# Sheet1.net
KiCad netlist of a schematic drawn in Altium Designer
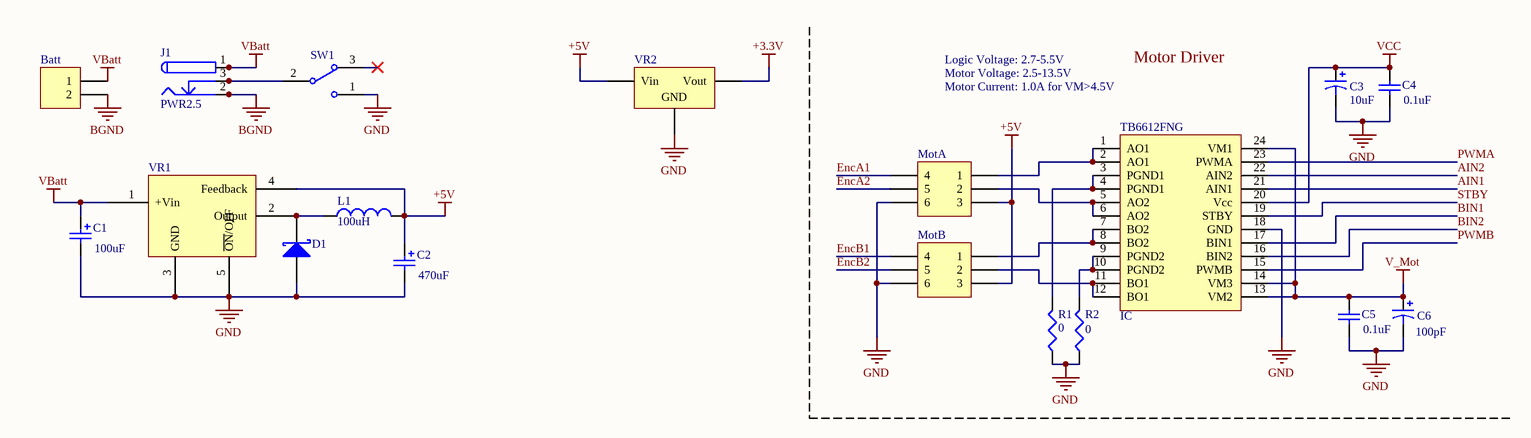
[diagram p0: Sheet1.SchDoc]

(export (version "E")
  (design (tool "Eeschema 10.0.6"))
  (components
    (comp (ref "Batt")
      (value "Header 2")
      (footprint "HDR1X2")
      (description "Header, 2-Pin")
      (fields (field (name "PUBLISHER") "Altium Limited"))
      (libsource (lib "Miscellaneous Connectors") (part "Header 2"))
    )
    (comp (ref "C1")
      (value "100uF")
      (footprint "Capacitor")
      (description "Polarized Capacitor (Radial)")
      (fields (field (name "Comment") "Cap Pol2") (field (name "PUBLISHER") "Altium Limited"))
      (libsource (lib "Miscellaneous Devices") (part "Cap Pol2"))
    )
    (comp (ref "C2")
      (value "470uF")
      (footprint "Capacitor - 8x10.5")
      (description "Polarized Capacitor (Radial)")
      (fields (field (name "Comment") "Cap Pol2") (field (name "PUBLISHER") "Altium Limited"))
      (libsource (lib "Miscellaneous Devices") (part "Cap Pol2"))
    )
    (comp (ref "C3")
      (value "10uF")
      (footprint "C0805")
      (description "Polarized Capacitor (Surface Mount)")
      (fields (field (name "Comment") "Cap Pol3") (field (name "PUBLISHER") "Altium Limited"))
      (libsource (lib "Miscellaneous Devices") (part "Cap Pol3"))
    )
    (comp (ref "C4")
      (value "0.1uF")
      (footprint "C1206")
      (description "Capacitor (Semiconductor SIM Model)")
      (fields (field (name "Comment") "Cap Semi") (field (name "PUBLISHER") "Altium Limited"))
      (libsource (lib "Miscellaneous Devices") (part "Cap Semi"))
    )
    (comp (ref "C5")
      (value "0.1uF")
      (footprint "C1206")
      (description "Capacitor (Semiconductor SIM Model)")
      (fields (field (name "Comment") "Cap Semi") (field (name "PUBLISHER") "Altium Limited"))
      (libsource (lib "Miscellaneous Devices") (part "Cap Semi"))
    )
    (comp (ref "C6")
      (value "100pF")
      (footprint "C0805")
      (description "Polarized Capacitor (Surface Mount)")
      (fields (field (name "Comment") "Cap Pol3") (field (name "PUBLISHER") "Altium Limited"))
      (libsource (lib "Miscellaneous Devices") (part "Cap Pol3"))
    )
    (comp (ref "D1")
      (value "D Schottky")
      (footprint "SMB")
      (description "Schottky Diode")
      (fields (field (name "PUBLISHER") "Altium Limited"))
      (libsource (lib "Miscellaneous Devices") (part "D Schottky"))
    )
    (comp (ref "J1")
      (value "PWR2.5")
      (footprint "KLD-0202")
      (description "Low Voltage Power Supply Connector")
      (fields (field (name "PUBLISHER") "Altium Limited"))
      (libsource (lib "Miscellaneous Connectors") (part "PWR2.5"))
    )
    (comp (ref "L1")
      (value "100uH")
      (footprint "0402-A")
      (description "Inductor")
      (fields (field (name "PUBLISHER") "Altium Limited"))
      (libsource (lib "Miscellaneous Devices") (part "Inductor"))
    )
    (comp (ref "MotA")
      (value "Header 3X2A")
      (footprint "HDR2X3_CEN")
      (description "Header, 3-Pin, Dual row")
      (fields (field (name "PUBLISHER") "Altium Limited"))
      (libsource (lib "Miscellaneous Connectors") (part "Header 3X2A"))
    )
    (comp (ref "MotB")
      (value "Header 3X2A")
      (footprint "HDR2X3_CEN")
      (description "Header, 3-Pin, Dual row")
      (fields (field (name "PUBLISHER") "Altium Limited"))
      (libsource (lib "Miscellaneous Connectors") (part "Header 3X2A"))
    )
    (comp (ref "R1")
      (value "0")
      (footprint "J1-0603")
      (description "Resistor")
      (fields (field (name "Comment") "Shunt Resistor") (field (name "PUBLISHER") "Altium Limited"))
      (libsource (lib "Miscellaneous Devices") (part "Res3"))
    )
    (comp (ref "R2")
      (value "0")
      (footprint "J1-0603")
      (description "Resistor")
      (fields (field (name "Comment") "Shunt Resistor") (field (name "PUBLISHER") "Altium Limited"))
      (libsource (lib "Miscellaneous Devices") (part "Res3"))
    )
    (comp (ref "SW1")
      (value "SW-SPDT")
      (footprint "TL36WW15050")
      (description "SPDT Subminiature Toggle Switch, Right Angle Mounting, Vertical Actuation")
      (fields (field (name "PUBLISHER") "Altium Limited"))
      (libsource (lib "Miscellaneous Devices") (part "SW-SPDT"))
    )
    (comp (ref "TB6612FNG")
      (value "IC")
      (description "Motor Driver IC")
      (libsource (lib "iRat") (part "TB6612FNG IC"))
    )
    (comp (ref "VR1")
      (value "LM2576S-5.0NOPB")
      (footprint "LM2576S")
      (description "5V Switching Regulator")
      (libsource (lib "iRat") (part "LM2576S-5.0NOPB"))
    )
    (comp (ref "VR2")
      (value "3V Volt Reg")
      (footprint "D2PAK_N")
      (description "Voltage Regulator")
      (fields (field (name "PUBLISHER") "Altium Limited"))
      (libsource (lib "Miscellaneous Devices") (part "Volt Reg"))
    )
  )
  (nets
    (net (code "1") (name "+3.3V") (class "Default")
      (node (ref "VR2") (pin "3") (pinfunction "Vout_3") (pintype "passive"))
    )
    (net (code "2") (name "+5V") (class "Default")
      (node (ref "C2") (pin "1") (pinfunction "1_1") (pintype "passive"))
      (node (ref "L1") (pin "2") (pinfunction "2_2") (pintype "passive"))
      (node (ref "MotA") (pin "3") (pinfunction "3_3") (pintype "passive"))
      (node (ref "MotB") (pin "3") (pinfunction "3_3") (pintype "passive"))
      (node (ref "VR1") (pin "4") (pinfunction "Feedback_4") (pintype "passive"))
      (node (ref "VR2") (pin "1") (pinfunction "Vin_1") (pintype "passive"))
    )
    (net (code "3") (name "/AIN1") (class "Default")
      (node (ref "TB6612FNG") (pin "21") (pinfunction "AIN1_21") (pintype "passive"))
    )
    (net (code "4") (name "/AIN2") (class "Default")
      (node (ref "TB6612FNG") (pin "22") (pinfunction "AIN2_22") (pintype "passive"))
    )
    (net (code "5") (name "/BIN1") (class "Default")
      (node (ref "TB6612FNG") (pin "17") (pinfunction "BIN1_17") (pintype "passive"))
    )
    (net (code "6") (name "/BIN2") (class "Default")
      (node (ref "TB6612FNG") (pin "16") (pinfunction "BIN2_16") (pintype "passive"))
    )
    (net (code "7") (name "/EncA1") (class "Default")
      (node (ref "MotA") (pin "4") (pinfunction "4_4") (pintype "passive"))
    )
    (net (code "8") (name "/EncA2") (class "Default")
      (node (ref "MotA") (pin "5") (pinfunction "5_5") (pintype "passive"))
    )
    (net (code "9") (name "/EncB1") (class "Default")
      (node (ref "MotB") (pin "4") (pinfunction "4_4") (pintype "passive"))
    )
    (net (code "10") (name "/EncB2") (class "Default")
      (node (ref "MotB") (pin "5") (pinfunction "5_5") (pintype "passive"))
    )
    (net (code "11") (name "/PWMA") (class "Default")
      (node (ref "TB6612FNG") (pin "23") (pinfunction "PWMA_23") (pintype "passive"))
    )
    (net (code "12") (name "/PWMB") (class "Default")
      (node (ref "TB6612FNG") (pin "15") (pinfunction "PWMB_15") (pintype "passive"))
    )
    (net (code "13") (name "/STBY") (class "Default")
      (node (ref "TB6612FNG") (pin "19") (pinfunction "STBY_19") (pintype "passive"))
    )
    (net (code "14") (name "BGND") (class "Default")
      (node (ref "Batt") (pin "2") (pinfunction "2_2") (pintype "passive"))
      (node (ref "J1") (pin "2") (pinfunction "2_2") (pintype "power_in"))
      (node (ref "J1") (pin "2A") (pinfunction "2A_2A") (pintype "power_in"))
      (node (ref "J1") (pin "2B") (pinfunction "2B_2B") (pintype "power_in"))
    )
    (net (code "15") (name "GND") (class "Default")
      (node (ref "C1") (pin "2") (pinfunction "2_2") (pintype "passive"))
      (node (ref "C2") (pin "2") (pinfunction "2_2") (pintype "passive"))
      (node (ref "C3") (pin "2") (pinfunction "2_2") (pintype "passive"))
      (node (ref "C4") (pin "2") (pinfunction "2_2") (pintype "passive"))
      (node (ref "C5") (pin "2") (pinfunction "2_2") (pintype "passive"))
      (node (ref "C6") (pin "2") (pinfunction "2_2") (pintype "passive"))
      (node (ref "D1") (pin "1") (pinfunction "A_1") (pintype "passive"))
      (node (ref "MotA") (pin "6") (pinfunction "6_6") (pintype "passive"))
      (node (ref "MotB") (pin "6") (pinfunction "6_6") (pintype "passive"))
      (node (ref "R1") (pin "1") (pinfunction "1_1") (pintype "passive"))
      (node (ref "R2") (pin "1") (pinfunction "1_1") (pintype "passive"))
      (node (ref "SW1") (pin "1") (pinfunction "1_1") (pintype "passive"))
      (node (ref "TB6612FNG") (pin "18") (pinfunction "GND_18") (pintype "passive"))
      (node (ref "VR1") (pin "3") (pinfunction "GND_3") (pintype "passive"))
      (node (ref "VR1") (pin "5") (pinfunction "~{ON}/OFF_5") (pintype "passive"))
      (node (ref "VR2") (pin "2") (pinfunction "GND_2") (pintype "passive"))
    )
    (net (code "16") (name "Net-(D1-K)") (class "Default")
      (node (ref "D1") (pin "2") (pinfunction "K_2") (pintype "passive"))
      (node (ref "L1") (pin "1") (pinfunction "1_1") (pintype "passive"))
      (node (ref "VR1") (pin "2") (pinfunction "Output_2") (pintype "passive"))
    )
    (net (code "17") (name "Net-(J1-Pad3)") (class "Default")
      (node (ref "J1") (pin "3") (pinfunction "3_3") (pintype "power_in"))
      (node (ref "J1") (pin "3A") (pinfunction "3A_3A") (pintype "power_in"))
      (node (ref "J1") (pin "3B") (pinfunction "3B_3B") (pintype "power_in"))
      (node (ref "SW1") (pin "2") (pinfunction "2_2") (pintype "passive"))
    )
    (net (code "18") (name "Net-(MotA-Pad1)") (class "Default")
      (node (ref "MotA") (pin "1") (pinfunction "1_1") (pintype "passive"))
      (node (ref "TB6612FNG") (pin "1") (pinfunction "AO1_1") (pintype "passive"))
      (node (ref "TB6612FNG") (pin "2") (pinfunction "AO1_2") (pintype "passive"))
    )
    (net (code "19") (name "Net-(MotA-Pad2)") (class "Default")
      (node (ref "MotA") (pin "2") (pinfunction "2_2") (pintype "passive"))
      (node (ref "TB6612FNG") (pin "5") (pinfunction "AO2_5") (pintype "passive"))
      (node (ref "TB6612FNG") (pin "6") (pinfunction "AO2_6") (pintype "passive"))
    )
    (net (code "20") (name "Net-(MotB-Pad1)") (class "Default")
      (node (ref "MotB") (pin "1") (pinfunction "1_1") (pintype "passive"))
      (node (ref "TB6612FNG") (pin "7") (pinfunction "BO2_7") (pintype "passive"))
      (node (ref "TB6612FNG") (pin "8") (pinfunction "BO2_8") (pintype "passive"))
    )
    (net (code "21") (name "Net-(MotB-Pad2)") (class "Default")
      (node (ref "MotB") (pin "2") (pinfunction "2_2") (pintype "passive"))
      (node (ref "TB6612FNG") (pin "11") (pinfunction "BO1_11") (pintype "passive"))
      (node (ref "TB6612FNG") (pin "12") (pinfunction "BO1_12") (pintype "passive"))
    )
    (net (code "22") (name "Net-(R1-Pad2)") (class "Default")
      (node (ref "R1") (pin "2") (pinfunction "2_2") (pintype "passive"))
      (node (ref "TB6612FNG") (pin "3") (pinfunction "PGND1_3") (pintype "passive"))
      (node (ref "TB6612FNG") (pin "4") (pinfunction "PGND1_4") (pintype "passive"))
    )
    (net (code "23") (name "Net-(R2-Pad2)") (class "Default")
      (node (ref "R2") (pin "2") (pinfunction "2_2") (pintype "passive"))
      (node (ref "TB6612FNG") (pin "10") (pinfunction "PGND2_10") (pintype "passive"))
      (node (ref "TB6612FNG") (pin "9") (pinfunction "PGND2_9") (pintype "passive"))
    )
    (net (code "24") (name "VBatt") (class "Default")
      (node (ref "Batt") (pin "1") (pinfunction "1_1") (pintype "passive"))
      (node (ref "C1") (pin "1") (pinfunction "1_1") (pintype "passive"))
      (node (ref "J1") (pin "1") (pinfunction "1_1") (pintype "power_in"))
      (node (ref "J1") (pin "1A") (pinfunction "1A_1A") (pintype "power_in"))
      (node (ref "J1") (pin "1B") (pinfunction "1B_1B") (pintype "power_in"))
      (node (ref "VR1") (pin "1") (pinfunction "+Vin_1") (pintype "passive"))
    )
    (net (code "25") (name "VCC") (class "Default")
      (node (ref "C3") (pin "1") (pinfunction "1_1") (pintype "passive"))
      (node (ref "C4") (pin "1") (pinfunction "1_1") (pintype "passive"))
      (node (ref "TB6612FNG") (pin "20") (pinfunction "Vcc_20") (pintype "passive"))
    )
    (net (code "26") (name "V_Mot") (class "Default")
      (node (ref "C5") (pin "1") (pinfunction "1_1") (pintype "passive"))
      (node (ref "C6") (pin "1") (pinfunction "1_1") (pintype "passive"))
      (node (ref "TB6612FNG") (pin "13") (pinfunction "VM2_13") (pintype "passive"))
      (node (ref "TB6612FNG") (pin "14") (pinfunction "VM3_14") (pintype "passive"))
      (node (ref "TB6612FNG") (pin "24") (pinfunction "VM1_24") (pintype "passive"))
    )
    (net (code "27") (name "unconnected-(SW1-Pad3)") (class "Default")
      (node (ref "SW1") (pin "3") (pinfunction "3_3") (pintype "passive+no_connect"))
    )
  )
)
